# coil-control-UNO-shield-v1.net
KiCad netlist of a schematic drawn in EAGLE
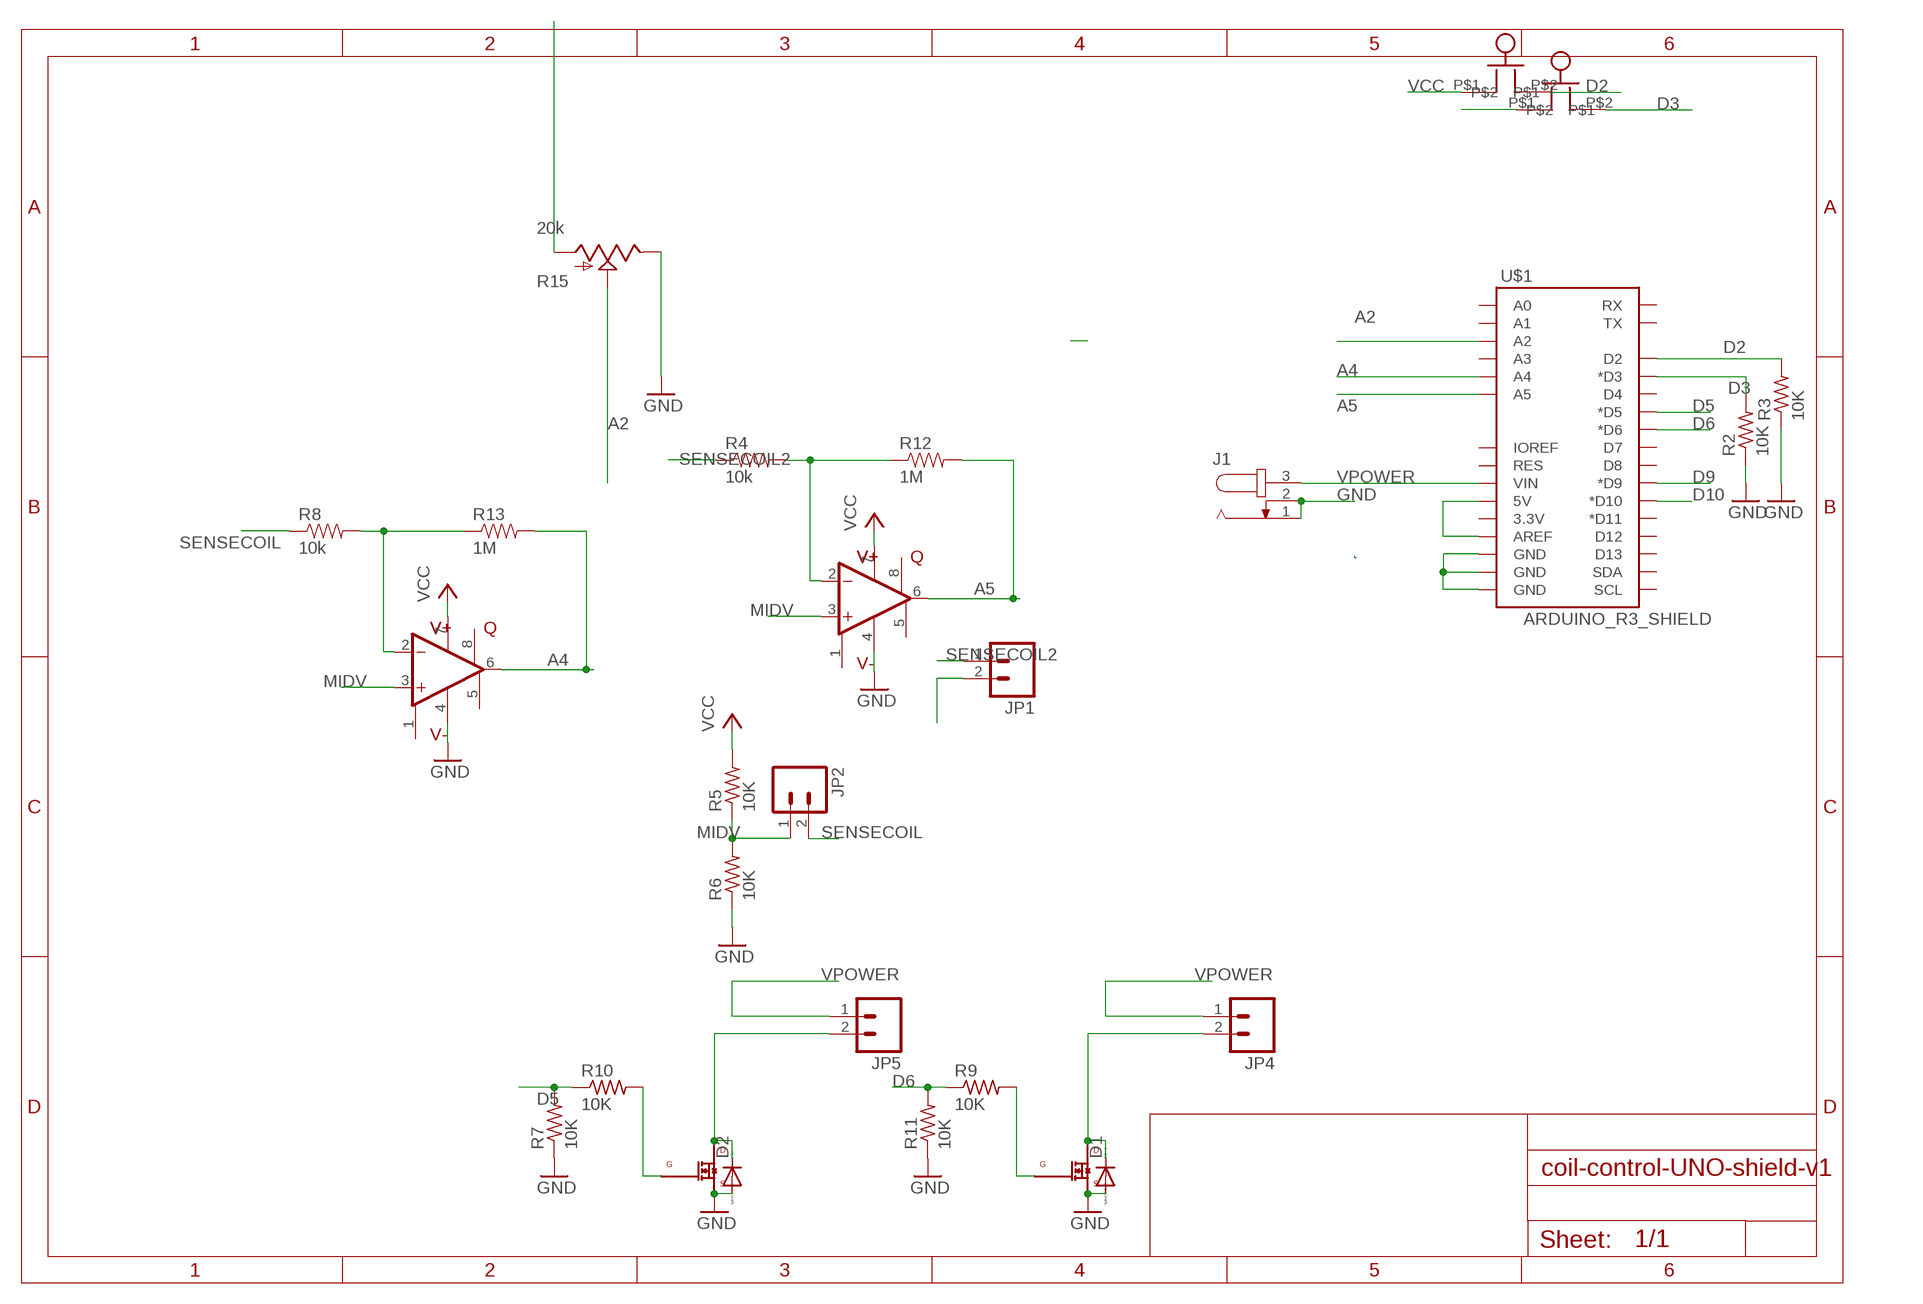
[diagram p0: schematic, sheet 1]

(export (version "E")
  (design (tool "Eeschema 10.0.6"))
  (components
    (comp (ref "D1")
      (value "DIODE-DO-214AC")
      (footprint "eagle-import:DO-214AC")
      (libsource (lib "eagle-import") (part "DIODE-DO-214AC"))
    )
    (comp (ref "D2")
      (value "DIODE-DO-214AC")
      (footprint "eagle-import:DO-214AC")
      (libsource (lib "eagle-import") (part "DIODE-DO-214AC"))
    )
    (comp (ref "J1")
      (value "JACK-PLUG1")
      (footprint "eagle-import:SPC4078")
      (libsource (lib "eagle-import") (part "JACK-PLUG1"))
    )
    (comp (ref "JP1")
      (value "M02PTH")
      (footprint "eagle-import:1X02")
      (libsource (lib "eagle-import") (part "M02PTH"))
    )
    (comp (ref "JP2")
      (value "M02PTH")
      (footprint "eagle-import:1X02")
      (libsource (lib "eagle-import") (part "M02PTH"))
    )
    (comp (ref "JP4")
      (value "M02PTH")
      (footprint "eagle-import:1X02")
      (libsource (lib "eagle-import") (part "M02PTH"))
    )
    (comp (ref "JP5")
      (value "M02PTH")
      (footprint "eagle-import:1X02")
      (libsource (lib "eagle-import") (part "M02PTH"))
    )
    (comp (ref "Q1")
      (value "IRLML0060")
      (footprint "eagle-import:SOT-23")
      (libsource (lib "eagle-import") (part "IRLML0060"))
    )
    (comp (ref "Q2")
      (value "IRLML0060")
      (footprint "eagle-import:SOT-23")
      (libsource (lib "eagle-import") (part "IRLML0060"))
    )
    (comp (ref "R2")
      (value "10K")
      (footprint "eagle-import:R0603")
      (libsource (lib "eagle-import") (part "R-US_R0603"))
    )
    (comp (ref "R3")
      (value "10K")
      (footprint "eagle-import:R0603")
      (libsource (lib "eagle-import") (part "R-US_R0603"))
    )
    (comp (ref "R4")
      (value "10k")
      (footprint "eagle-import:0603-RES")
      (libsource (lib "eagle-import") (part "RESISTOR0603"))
    )
    (comp (ref "R5")
      (value "10K")
      (footprint "eagle-import:R0603")
      (libsource (lib "eagle-import") (part "R-US_R0603"))
    )
    (comp (ref "R6")
      (value "10K")
      (footprint "eagle-import:R0603")
      (libsource (lib "eagle-import") (part "R-US_R0603"))
    )
    (comp (ref "R7")
      (value "10K")
      (footprint "eagle-import:R0603")
      (libsource (lib "eagle-import") (part "R-US_R0603"))
    )
    (comp (ref "R8")
      (value "10k")
      (footprint "eagle-import:0603-RES")
      (libsource (lib "eagle-import") (part "RESISTOR0603"))
    )
    (comp (ref "R9")
      (value "10K")
      (footprint "eagle-import:R0603")
      (libsource (lib "eagle-import") (part "R-US_R0603"))
    )
    (comp (ref "R10")
      (value "10K")
      (footprint "eagle-import:R0603")
      (libsource (lib "eagle-import") (part "R-US_R0603"))
    )
    (comp (ref "R11")
      (value "10K")
      (footprint "eagle-import:R0603")
      (libsource (lib "eagle-import") (part "R-US_R0603"))
    )
    (comp (ref "R12")
      (value "1M")
      (footprint "eagle-import:0805")
      (libsource (lib "eagle-import") (part "RESISTOR0805-RES"))
    )
    (comp (ref "R13")
      (value "1M")
      (footprint "eagle-import:0805")
      (libsource (lib "eagle-import") (part "RESISTOR0805-RES"))
    )
    (comp (ref "R15")
      (value "20k")
      (footprint "eagle-import:ALPS_POT_KIT")
      (libsource (lib "eagle-import") (part "POTALPS-KIT"))
    )
    (comp (ref "SW2")
      (value "BUTTON")
      (footprint "eagle-import:BUTTON")
      (libsource (lib "eagle-import") (part "BUTTON"))
    )
    (comp (ref "SW3")
      (value "BUTTON")
      (footprint "eagle-import:BUTTON")
      (libsource (lib "eagle-import") (part "BUTTON"))
    )
    (comp (ref "U$1")
      (value "ARDUINO_R3_SHIELD")
      (footprint "eagle-import:UNO_R3_SHIELD")
      (libsource (lib "eagle-import") (part "ARDUINO_R3_SHIELD"))
    )
    (comp (ref "U2")
      (value "LM4250")
      (footprint "eagle-import:DIP08")
      (libsource (lib "eagle-import") (part "LM4250"))
    )
    (comp (ref "U3")
      (value "LM4250")
      (footprint "eagle-import:DIP08")
      (libsource (lib "eagle-import") (part "LM4250"))
    )
  )
  (nets
    (net (code "1") (name "/A2") (class "Default")
      (node (ref "R15") (pin "P$2") (pinfunction "S_P$2") (pintype "passive"))
      (node (ref "U$1") (pin "A2") (pinfunction "A2_A2") (pintype "bidirectional"))
    )
    (net (code "2") (name "/A4") (class "Default")
      (node (ref "R13") (pin "2") (pinfunction "2_2") (pintype "passive"))
      (node (ref "U$1") (pin "A4") (pinfunction "A4_A4") (pintype "bidirectional"))
      (node (ref "U2") (pin "6") (pinfunction "OUT_6") (pintype "output"))
    )
    (net (code "3") (name "/A5") (class "Default")
      (node (ref "R12") (pin "2") (pinfunction "2_2") (pintype "passive"))
      (node (ref "U$1") (pin "A5") (pinfunction "A5_A5") (pintype "bidirectional"))
      (node (ref "U3") (pin "6") (pinfunction "OUT_6") (pintype "output"))
    )
    (net (code "4") (name "/D2") (class "Default")
      (node (ref "R3") (pin "2") (pinfunction "2_2") (pintype "passive"))
      (node (ref "SW2") (pin "P$2") (pinfunction "P$2_P$2") (pintype "bidirectional"))
      (node (ref "U$1") (pin "D2") (pinfunction "D2_D2") (pintype "bidirectional"))
    )
    (net (code "5") (name "/D3") (class "Default")
      (node (ref "R2") (pin "2") (pinfunction "2_2") (pintype "passive"))
      (node (ref "SW3") (pin "P$2") (pinfunction "P$2_P$2") (pintype "bidirectional"))
      (node (ref "U$1") (pin "D3") (pinfunction "*D3_D3") (pintype "bidirectional"))
    )
    (net (code "6") (name "/D5") (class "Default")
      (node (ref "R10") (pin "1") (pinfunction "1_1") (pintype "passive"))
      (node (ref "R7") (pin "2") (pinfunction "2_2") (pintype "passive"))
      (node (ref "U$1") (pin "D5") (pinfunction "*D5_D5") (pintype "bidirectional"))
    )
    (net (code "7") (name "/D6") (class "Default")
      (node (ref "R11") (pin "2") (pinfunction "2_2") (pintype "passive"))
      (node (ref "R9") (pin "1") (pinfunction "1_1") (pintype "passive"))
      (node (ref "U$1") (pin "D6") (pinfunction "*D6_D6") (pintype "bidirectional"))
    )
    (net (code "8") (name "/D9") (class "Default")
      (node (ref "U$1") (pin "D9") (pinfunction "*D9_D9") (pintype "bidirectional"))
    )
    (net (code "9") (name "/D10") (class "Default")
      (node (ref "U$1") (pin "D10") (pinfunction "*D10_D10") (pintype "bidirectional"))
    )
    (net (code "10") (name "/MIDV") (class "Default")
      (node (ref "JP1") (pin "2") (pinfunction "2_2") (pintype "passive"))
      (node (ref "JP2") (pin "1") (pinfunction "1_1") (pintype "passive"))
      (node (ref "R5") (pin "1") (pinfunction "1_1") (pintype "passive"))
      (node (ref "R6") (pin "2") (pinfunction "2_2") (pintype "passive"))
      (node (ref "U2") (pin "3") (pinfunction "+IN_3") (pintype "input"))
      (node (ref "U3") (pin "3") (pinfunction "+IN_3") (pintype "input"))
    )
    (net (code "11") (name "/SENSECOIL") (class "Default")
      (node (ref "JP2") (pin "2") (pinfunction "2_2") (pintype "passive"))
      (node (ref "R8") (pin "1") (pinfunction "1_1") (pintype "passive"))
    )
    (net (code "12") (name "/SENSECOIL2") (class "Default")
      (node (ref "JP1") (pin "1") (pinfunction "1_1") (pintype "passive"))
      (node (ref "R4") (pin "1") (pinfunction "1_1") (pintype "passive"))
    )
    (net (code "13") (name "/VPOWER") (class "Default")
      (node (ref "J1") (pin "3") (pinfunction "3_3") (pintype "passive"))
      (node (ref "JP4") (pin "1") (pinfunction "1_1") (pintype "passive"))
      (node (ref "JP5") (pin "1") (pinfunction "1_1") (pintype "passive"))
      (node (ref "U$1") (pin "VIN") (pinfunction "VIN_VIN") (pintype "bidirectional"))
    )
    (net (code "14") (name "GND") (class "Default")
      (node (ref "D1") (pin "A") (pinfunction "A_A") (pintype "passive"))
      (node (ref "D2") (pin "A") (pinfunction "A_A") (pintype "passive"))
      (node (ref "J1") (pin "1") (pinfunction "1_1") (pintype "passive"))
      (node (ref "J1") (pin "2") (pinfunction "2_2") (pintype "passive"))
      (node (ref "Q1") (pin "2") (pinfunction "SOURCE_2") (pintype "bidirectional"))
      (node (ref "Q2") (pin "2") (pinfunction "SOURCE_2") (pintype "bidirectional"))
      (node (ref "R11") (pin "1") (pinfunction "1_1") (pintype "passive"))
      (node (ref "R15") (pin "P$1") (pinfunction "E_P$1") (pintype "passive"))
      (node (ref "R2") (pin "1") (pinfunction "1_1") (pintype "passive"))
      (node (ref "R3") (pin "1") (pinfunction "1_1") (pintype "passive"))
      (node (ref "R6") (pin "1") (pinfunction "1_1") (pintype "passive"))
      (node (ref "R7") (pin "1") (pinfunction "1_1") (pintype "passive"))
      (node (ref "U$1") (pin "GND@0") (pinfunction "GND_GND@0") (pintype "bidirectional"))
      (node (ref "U$1") (pin "GND@1") (pinfunction "GND_GND@1") (pintype "bidirectional"))
      (node (ref "U$1") (pin "GND@2") (pinfunction "GND_GND@2") (pintype "bidirectional"))
      (node (ref "U2") (pin "4") (pinfunction "V-_4") (pintype "power_in"))
      (node (ref "U3") (pin "4") (pinfunction "V-_4") (pintype "power_in"))
    )
    (net (code "15") (name "Net-(Q1-DRAIN)") (class "Default")
      (node (ref "D1") (pin "C") (pinfunction "C_C") (pintype "passive"))
      (node (ref "JP4") (pin "2") (pinfunction "2_2") (pintype "passive"))
      (node (ref "Q1") (pin "3") (pinfunction "DRAIN_3") (pintype "bidirectional"))
    )
    (net (code "16") (name "Net-(Q1-GATE)") (class "Default")
      (node (ref "Q1") (pin "1") (pinfunction "GATE_1") (pintype "bidirectional"))
      (node (ref "R9") (pin "2") (pinfunction "2_2") (pintype "passive"))
    )
    (net (code "17") (name "Net-(Q2-DRAIN)") (class "Default")
      (node (ref "D2") (pin "C") (pinfunction "C_C") (pintype "passive"))
      (node (ref "JP5") (pin "2") (pinfunction "2_2") (pintype "passive"))
      (node (ref "Q2") (pin "3") (pinfunction "DRAIN_3") (pintype "bidirectional"))
    )
    (net (code "18") (name "Net-(Q2-GATE)") (class "Default")
      (node (ref "Q2") (pin "1") (pinfunction "GATE_1") (pintype "bidirectional"))
      (node (ref "R10") (pin "2") (pinfunction "2_2") (pintype "passive"))
    )
    (net (code "19") (name "Net-(U2--IN)") (class "Default")
      (node (ref "R13") (pin "1") (pinfunction "1_1") (pintype "passive"))
      (node (ref "R8") (pin "2") (pinfunction "2_2") (pintype "passive"))
      (node (ref "U2") (pin "2") (pinfunction "-IN_2") (pintype "input"))
    )
    (net (code "20") (name "Net-(U3--IN)") (class "Default")
      (node (ref "R12") (pin "1") (pinfunction "1_1") (pintype "passive"))
      (node (ref "R4") (pin "2") (pinfunction "2_2") (pintype "passive"))
      (node (ref "U3") (pin "2") (pinfunction "-IN_2") (pintype "input"))
    )
    (net (code "21") (name "VCC") (class "Default")
      (node (ref "R15") (pin "P$3") (pinfunction "A_P$3") (pintype "passive"))
      (node (ref "R5") (pin "2") (pinfunction "2_2") (pintype "passive"))
      (node (ref "SW2") (pin "P$1") (pinfunction "P$1_P$1") (pintype "bidirectional"))
      (node (ref "SW3") (pin "P$1") (pinfunction "P$1_P$1") (pintype "bidirectional"))
      (node (ref "U$1") (pin "5V") (pinfunction "5V_5V") (pintype "bidirectional"))
      (node (ref "U$1") (pin "AREF") (pinfunction "AREF_AREF") (pintype "bidirectional"))
      (node (ref "U2") (pin "7") (pinfunction "V+_7") (pintype "power_in"))
      (node (ref "U3") (pin "7") (pinfunction "V+_7") (pintype "power_in"))
    )
    (net (code "22") (name "unconnected-(U$1-*D11-PadD11)") (class "Default")
      (node (ref "U$1") (pin "D11") (pinfunction "*D11_D11") (pintype "bidirectional"))
    )
    (net (code "23") (name "unconnected-(U$1-Pad3.3V)") (class "Default")
      (node (ref "U$1") (pin "3.3V") (pinfunction "3.3V_3.3V") (pintype "bidirectional"))
    )
    (net (code "24") (name "unconnected-(U$1-PadA0)") (class "Default")
      (node (ref "U$1") (pin "A0") (pinfunction "A0_A0") (pintype "bidirectional"))
    )
    (net (code "25") (name "unconnected-(U$1-PadA1)") (class "Default")
      (node (ref "U$1") (pin "A1") (pinfunction "A1_A1") (pintype "bidirectional"))
    )
    (net (code "26") (name "unconnected-(U$1-PadA3)") (class "Default")
      (node (ref "U$1") (pin "A3") (pinfunction "A3_A3") (pintype "bidirectional"))
    )
    (net (code "27") (name "unconnected-(U$1-PadD4)") (class "Default")
      (node (ref "U$1") (pin "D4") (pinfunction "D4_D4") (pintype "bidirectional"))
    )
    (net (code "28") (name "unconnected-(U$1-PadD7)") (class "Default")
      (node (ref "U$1") (pin "D7") (pinfunction "D7_D7") (pintype "bidirectional"))
    )
    (net (code "29") (name "unconnected-(U$1-PadD8)") (class "Default")
      (node (ref "U$1") (pin "D8") (pinfunction "D8_D8") (pintype "bidirectional"))
    )
    (net (code "30") (name "unconnected-(U$1-PadD12)") (class "Default")
      (node (ref "U$1") (pin "D12") (pinfunction "D12_D12") (pintype "bidirectional"))
    )
    (net (code "31") (name "unconnected-(U$1-PadD13)") (class "Default")
      (node (ref "U$1") (pin "D13") (pinfunction "D13_D13") (pintype "bidirectional"))
    )
    (net (code "32") (name "unconnected-(U$1-PadIOREF)") (class "Default")
      (node (ref "U$1") (pin "IOREF") (pinfunction "IOREF_IOREF") (pintype "bidirectional"))
    )
    (net (code "33") (name "unconnected-(U$1-PadRES)") (class "Default")
      (node (ref "U$1") (pin "RES") (pinfunction "RES_RES") (pintype "bidirectional"))
    )
    (net (code "34") (name "unconnected-(U$1-PadRX)") (class "Default")
      (node (ref "U$1") (pin "RX") (pinfunction "RX_RX") (pintype "bidirectional"))
    )
    (net (code "35") (name "unconnected-(U$1-PadSCL)") (class "Default")
      (node (ref "U$1") (pin "SCL") (pinfunction "SCL_SCL") (pintype "bidirectional"))
    )
    (net (code "36") (name "unconnected-(U$1-PadSDA)") (class "Default")
      (node (ref "U$1") (pin "SDA") (pinfunction "SDA_SDA") (pintype "bidirectional"))
    )
    (net (code "37") (name "unconnected-(U$1-PadTX)") (class "Default")
      (node (ref "U$1") (pin "TX") (pinfunction "TX_TX") (pintype "bidirectional"))
    )
    (net (code "38") (name "unconnected-(U2-NULL1-Pad1)") (class "Default")
      (node (ref "U2") (pin "1") (pinfunction "NULL1_1") (pintype "bidirectional"))
    )
    (net (code "39") (name "unconnected-(U2-NULL2-Pad5)") (class "Default")
      (node (ref "U2") (pin "5") (pinfunction "NULL2_5") (pintype "bidirectional"))
    )
    (net (code "40") (name "unconnected-(U2-QUIES-Pad8)") (class "Default")
      (node (ref "U2") (pin "8") (pinfunction "QUIES_8") (pintype "bidirectional"))
    )
    (net (code "41") (name "unconnected-(U3-NULL1-Pad1)") (class "Default")
      (node (ref "U3") (pin "1") (pinfunction "NULL1_1") (pintype "bidirectional"))
    )
    (net (code "42") (name "unconnected-(U3-NULL2-Pad5)") (class "Default")
      (node (ref "U3") (pin "5") (pinfunction "NULL2_5") (pintype "bidirectional"))
    )
    (net (code "43") (name "unconnected-(U3-QUIES-Pad8)") (class "Default")
      (node (ref "U3") (pin "8") (pinfunction "QUIES_8") (pintype "bidirectional"))
    )
  )
)
